# nandboard.net
KiCad netlist of a schematic drawn in EAGLE
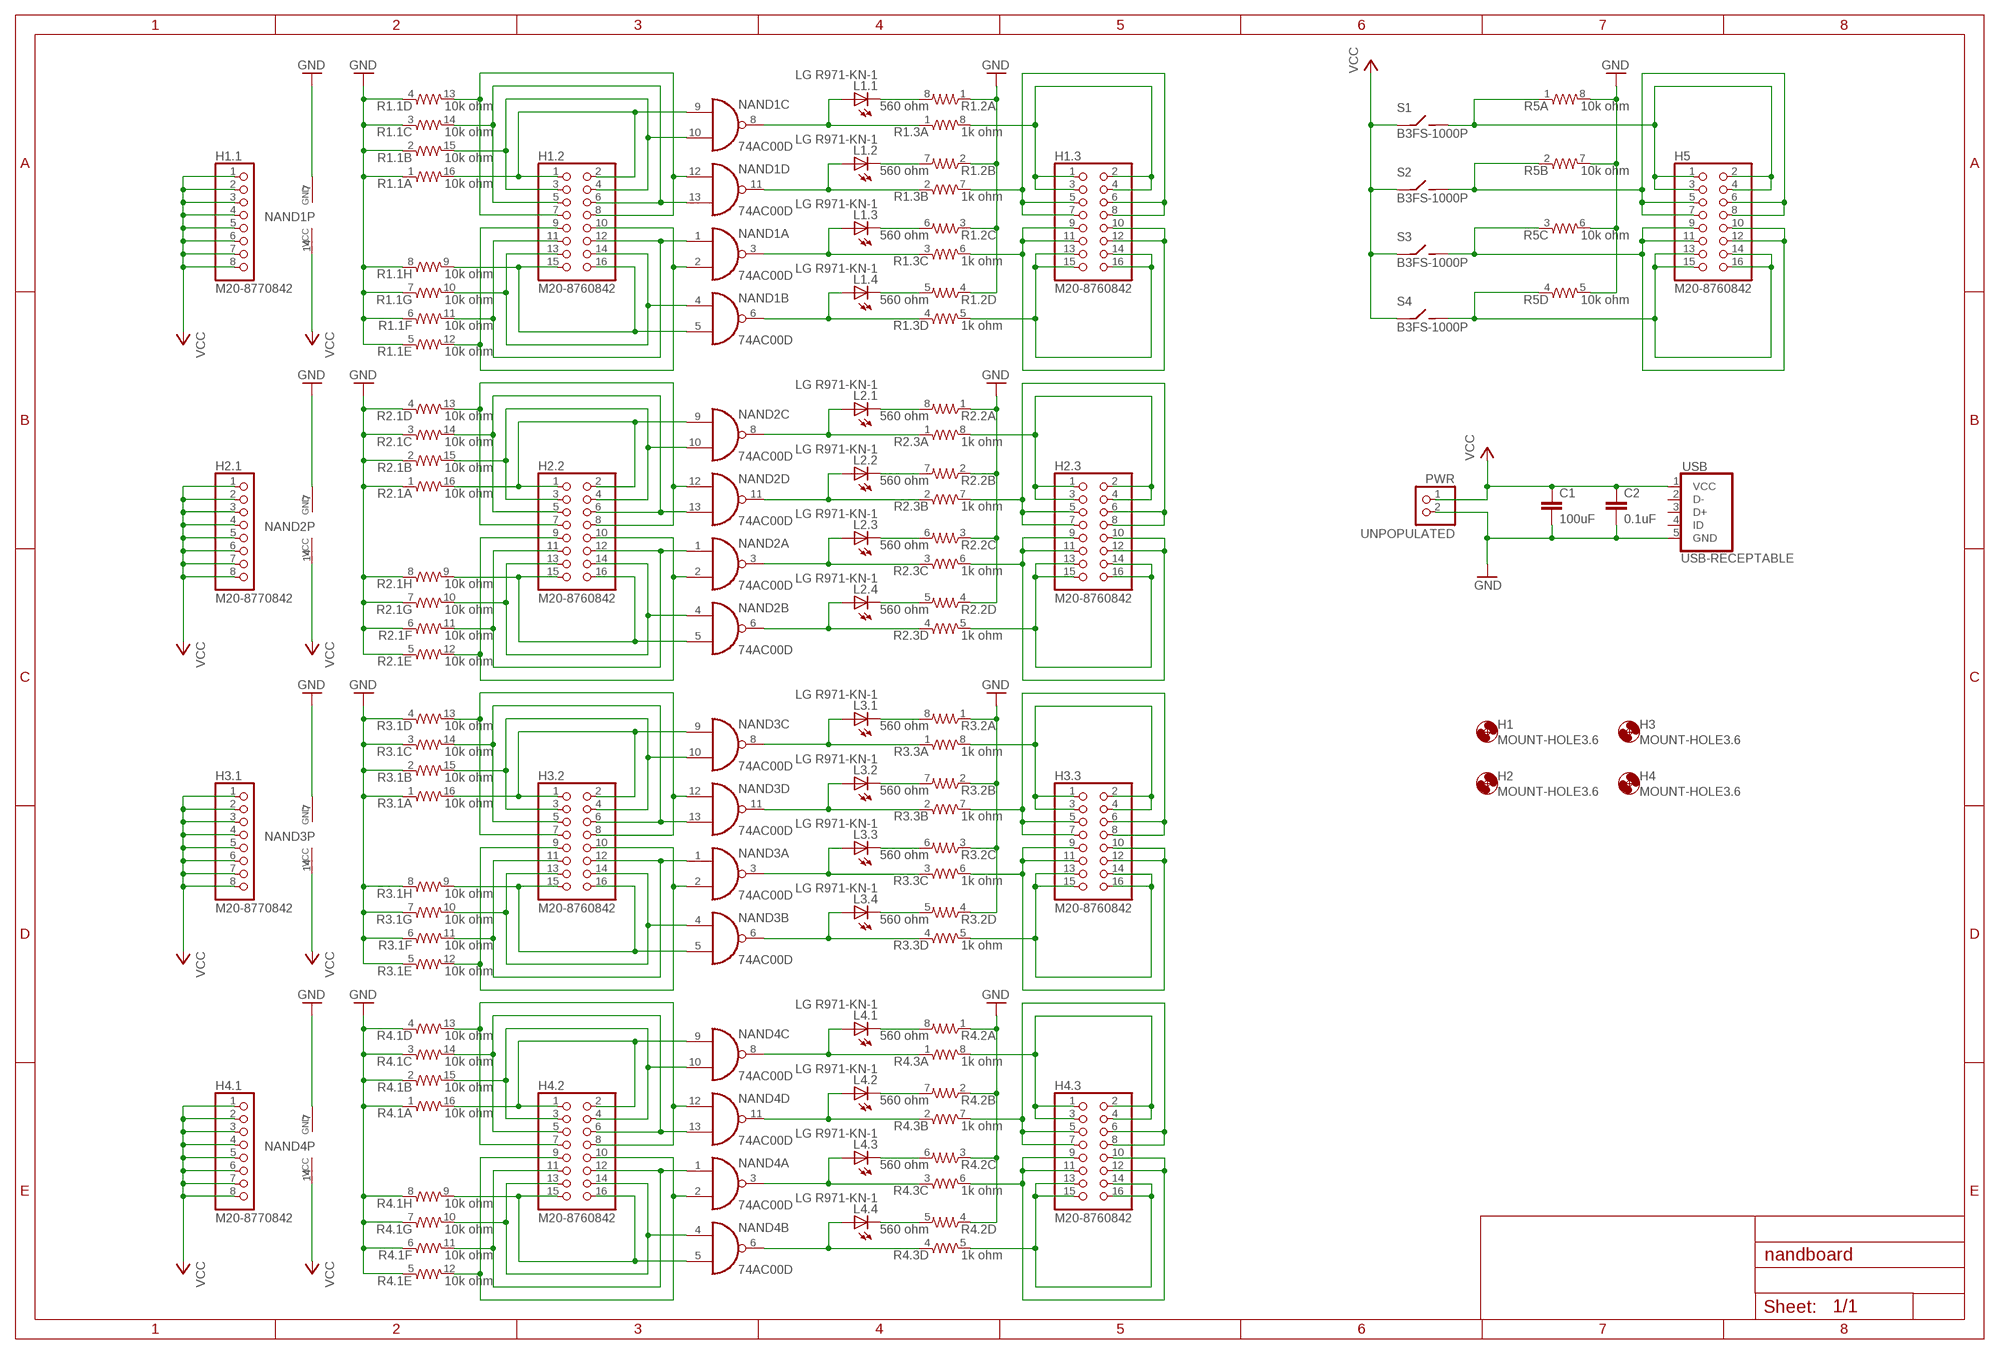
[diagram p0: schematic, sheet 1]

(export (version "E")
  (design (tool "Eeschema 10.0.6"))
  (components
    (comp (ref "C1")
      (value "100uF")
      (footprint "eagle-import:C1210")
      (libsource (lib "eagle-import") (part "C-EUC1210"))
    )
    (comp (ref "C2")
      (value "0.1uF")
      (footprint "eagle-import:C0805")
      (libsource (lib "eagle-import") (part "C-EUC0805"))
    )
    (comp (ref "H1")
      (value "MOUNT-HOLE3.6")
      (footprint "eagle-import:3,6")
      (libsource (lib "eagle-import") (part "MOUNT-HOLE3.6"))
    )
    (comp (ref "H1.1")
      (value "M20-8770842")
      (footprint "eagle-import:1X08_SMT")
      (libsource (lib "eagle-import") (part "PINHD-1X81X08_SMT"))
    )
    (comp (ref "H1.2")
      (value "M20-8760842")
      (footprint "eagle-import:2X08_SMT")
      (libsource (lib "eagle-import") (part "PINHD-2X8SMT"))
    )
    (comp (ref "H1.3")
      (value "M20-8760842")
      (footprint "eagle-import:2X08_SMT")
      (libsource (lib "eagle-import") (part "PINHD-2X8SMT"))
    )
    (comp (ref "H2")
      (value "MOUNT-HOLE3.6")
      (footprint "eagle-import:3,6")
      (libsource (lib "eagle-import") (part "MOUNT-HOLE3.6"))
    )
    (comp (ref "H2.1")
      (value "M20-8770842")
      (footprint "eagle-import:1X08_SMT")
      (libsource (lib "eagle-import") (part "PINHD-1X81X08_SMT"))
    )
    (comp (ref "H2.2")
      (value "M20-8760842")
      (footprint "eagle-import:2X08_SMT")
      (libsource (lib "eagle-import") (part "PINHD-2X8SMT"))
    )
    (comp (ref "H2.3")
      (value "M20-8760842")
      (footprint "eagle-import:2X08_SMT")
      (libsource (lib "eagle-import") (part "PINHD-2X8SMT"))
    )
    (comp (ref "H3")
      (value "MOUNT-HOLE3.6")
      (footprint "eagle-import:3,6")
      (libsource (lib "eagle-import") (part "MOUNT-HOLE3.6"))
    )
    (comp (ref "H3.1")
      (value "M20-8770842")
      (footprint "eagle-import:1X08_SMT")
      (libsource (lib "eagle-import") (part "PINHD-1X81X08_SMT"))
    )
    (comp (ref "H3.2")
      (value "M20-8760842")
      (footprint "eagle-import:2X08_SMT")
      (libsource (lib "eagle-import") (part "PINHD-2X8SMT"))
    )
    (comp (ref "H3.3")
      (value "M20-8760842")
      (footprint "eagle-import:2X08_SMT")
      (libsource (lib "eagle-import") (part "PINHD-2X8SMT"))
    )
    (comp (ref "H4")
      (value "MOUNT-HOLE3.6")
      (footprint "eagle-import:3,6")
      (libsource (lib "eagle-import") (part "MOUNT-HOLE3.6"))
    )
    (comp (ref "H4.1")
      (value "M20-8770842")
      (footprint "eagle-import:1X08_SMT")
      (libsource (lib "eagle-import") (part "PINHD-1X81X08_SMT"))
    )
    (comp (ref "H4.2")
      (value "M20-8760842")
      (footprint "eagle-import:2X08_SMT")
      (libsource (lib "eagle-import") (part "PINHD-2X8SMT"))
    )
    (comp (ref "H4.3")
      (value "M20-8760842")
      (footprint "eagle-import:2X08_SMT")
      (libsource (lib "eagle-import") (part "PINHD-2X8SMT"))
    )
    (comp (ref "H5")
      (value "M20-8760842")
      (footprint "eagle-import:2X08_SMT")
      (libsource (lib "eagle-import") (part "PINHD-2X8SMT"))
    )
    (comp (ref "L1.1")
      (value "LG R971-KN-1")
      (footprint "eagle-import:CHIPLED_0805")
      (libsource (lib "eagle-import") (part "LEDCHIPLED_0805"))
    )
    (comp (ref "L1.2")
      (value "LG R971-KN-1")
      (footprint "eagle-import:CHIPLED_0805")
      (libsource (lib "eagle-import") (part "LEDCHIPLED_0805"))
    )
    (comp (ref "L1.3")
      (value "LG R971-KN-1")
      (footprint "eagle-import:CHIPLED_0805")
      (libsource (lib "eagle-import") (part "LEDCHIPLED_0805"))
    )
    (comp (ref "L1.4")
      (value "LG R971-KN-1")
      (footprint "eagle-import:CHIPLED_0805")
      (libsource (lib "eagle-import") (part "LEDCHIPLED_0805"))
    )
    (comp (ref "L2.1")
      (value "LG R971-KN-1")
      (footprint "eagle-import:CHIPLED_0805")
      (libsource (lib "eagle-import") (part "LEDCHIPLED_0805"))
    )
    (comp (ref "L2.2")
      (value "LG R971-KN-1")
      (footprint "eagle-import:CHIPLED_0805")
      (libsource (lib "eagle-import") (part "LEDCHIPLED_0805"))
    )
    (comp (ref "L2.3")
      (value "LG R971-KN-1")
      (footprint "eagle-import:CHIPLED_0805")
      (libsource (lib "eagle-import") (part "LEDCHIPLED_0805"))
    )
    (comp (ref "L2.4")
      (value "LG R971-KN-1")
      (footprint "eagle-import:CHIPLED_0805")
      (libsource (lib "eagle-import") (part "LEDCHIPLED_0805"))
    )
    (comp (ref "L3.1")
      (value "LG R971-KN-1")
      (footprint "eagle-import:CHIPLED_0805")
      (libsource (lib "eagle-import") (part "LEDCHIPLED_0805"))
    )
    (comp (ref "L3.2")
      (value "LG R971-KN-1")
      (footprint "eagle-import:CHIPLED_0805")
      (libsource (lib "eagle-import") (part "LEDCHIPLED_0805"))
    )
    (comp (ref "L3.3")
      (value "LG R971-KN-1")
      (footprint "eagle-import:CHIPLED_0805")
      (libsource (lib "eagle-import") (part "LEDCHIPLED_0805"))
    )
    (comp (ref "L3.4")
      (value "LG R971-KN-1")
      (footprint "eagle-import:CHIPLED_0805")
      (libsource (lib "eagle-import") (part "LEDCHIPLED_0805"))
    )
    (comp (ref "L4.1")
      (value "LG R971-KN-1")
      (footprint "eagle-import:CHIPLED_0805")
      (libsource (lib "eagle-import") (part "LEDCHIPLED_0805"))
    )
    (comp (ref "L4.2")
      (value "LG R971-KN-1")
      (footprint "eagle-import:CHIPLED_0805")
      (libsource (lib "eagle-import") (part "LEDCHIPLED_0805"))
    )
    (comp (ref "L4.3")
      (value "LG R971-KN-1")
      (footprint "eagle-import:CHIPLED_0805")
      (libsource (lib "eagle-import") (part "LEDCHIPLED_0805"))
    )
    (comp (ref "L4.4")
      (value "LG R971-KN-1")
      (footprint "eagle-import:CHIPLED_0805")
      (libsource (lib "eagle-import") (part "LEDCHIPLED_0805"))
    )
    (comp (ref "NAND1")
      (value "74AC00D")
      (footprint "eagle-import:SO14")
      (libsource (lib "eagle-import") (part "7400DAC"))
    )
    (comp (ref "NAND2")
      (value "74AC00D")
      (footprint "eagle-import:SO14")
      (libsource (lib "eagle-import") (part "7400DAC"))
    )
    (comp (ref "NAND3")
      (value "74AC00D")
      (footprint "eagle-import:SO14")
      (libsource (lib "eagle-import") (part "7400DAC"))
    )
    (comp (ref "NAND4")
      (value "74AC00D")
      (footprint "eagle-import:SO14")
      (libsource (lib "eagle-import") (part "7400DAC"))
    )
    (comp (ref "PWR")
      (value "UNPOPULATED")
      (footprint "eagle-import:1X02")
      (libsource (lib "eagle-import") (part "PINHD-1X2"))
    )
    (comp (ref "R1.1")
      (value "10k ohm")
      (footprint "eagle-import:742-16")
      (libsource (lib "eagle-import") (part "742-16_S"))
    )
    (comp (ref "R1.2")
      (value "560 ohm")
      (footprint "eagle-import:742-8")
      (libsource (lib "eagle-import") (part "742-8_S"))
    )
    (comp (ref "R1.3")
      (value "1k ohm")
      (footprint "eagle-import:742-8")
      (libsource (lib "eagle-import") (part "742-8_S"))
    )
    (comp (ref "R2.1")
      (value "10k ohm")
      (footprint "eagle-import:742-16")
      (libsource (lib "eagle-import") (part "742-16_S"))
    )
    (comp (ref "R2.2")
      (value "560 ohm")
      (footprint "eagle-import:742-8")
      (libsource (lib "eagle-import") (part "742-8_S"))
    )
    (comp (ref "R2.3")
      (value "1k ohm")
      (footprint "eagle-import:742-8")
      (libsource (lib "eagle-import") (part "742-8_S"))
    )
    (comp (ref "R3.1")
      (value "10k ohm")
      (footprint "eagle-import:742-16")
      (libsource (lib "eagle-import") (part "742-16_S"))
    )
    (comp (ref "R3.2")
      (value "560 ohm")
      (footprint "eagle-import:742-8")
      (libsource (lib "eagle-import") (part "742-8_S"))
    )
    (comp (ref "R3.3")
      (value "1k ohm")
      (footprint "eagle-import:742-8")
      (libsource (lib "eagle-import") (part "742-8_S"))
    )
    (comp (ref "R4.1")
      (value "10k ohm")
      (footprint "eagle-import:742-16")
      (libsource (lib "eagle-import") (part "742-16_S"))
    )
    (comp (ref "R4.2")
      (value "560 ohm")
      (footprint "eagle-import:742-8")
      (libsource (lib "eagle-import") (part "742-8_S"))
    )
    (comp (ref "R4.3")
      (value "1k ohm")
      (footprint "eagle-import:742-8")
      (libsource (lib "eagle-import") (part "742-8_S"))
    )
    (comp (ref "R5")
      (value "10k ohm")
      (footprint "eagle-import:742-8")
      (libsource (lib "eagle-import") (part "742-8_S"))
    )
    (comp (ref "S1")
      (value "B3FS-1000P")
      (footprint "eagle-import:B3FS-1000")
      (libsource (lib "eagle-import") (part "SPSTB3FS-1000"))
    )
    (comp (ref "S2")
      (value "B3FS-1000P")
      (footprint "eagle-import:B3FS-1000")
      (libsource (lib "eagle-import") (part "SPSTB3FS-1000"))
    )
    (comp (ref "S3")
      (value "B3FS-1000P")
      (footprint "eagle-import:B3FS-1000")
      (libsource (lib "eagle-import") (part "SPSTB3FS-1000"))
    )
    (comp (ref "S4")
      (value "B3FS-1000P")
      (footprint "eagle-import:B3FS-1000")
      (libsource (lib "eagle-import") (part "SPSTB3FS-1000"))
    )
    (comp (ref "USB")
      (value "USB-RECEPTABLE")
      (footprint "eagle-import:FCI-10103594-0001LF")
      (libsource (lib "eagle-import") (part "USB-RECEPTABLE"))
    )
  )
  (nets
    (net (code "1") (name "GND") (class "Default")
      (node (ref "C1") (pin "2") (pinfunction "2_2") (pintype "passive"))
      (node (ref "C2") (pin "2") (pinfunction "2_2") (pintype "passive"))
      (node (ref "NAND1") (pin "7") (pinfunction "GND_7") (pintype "power_in"))
      (node (ref "NAND2") (pin "7") (pinfunction "GND_7") (pintype "power_in"))
      (node (ref "NAND3") (pin "7") (pinfunction "GND_7") (pintype "power_in"))
      (node (ref "NAND4") (pin "7") (pinfunction "GND_7") (pintype "power_in"))
      (node (ref "PWR") (pin "2") (pinfunction "2_2") (pintype "passive"))
      (node (ref "R1.1") (pin "1") (pinfunction "1_1") (pintype "passive"))
      (node (ref "R1.1") (pin "2") (pinfunction "1_2") (pintype "passive"))
      (node (ref "R1.1") (pin "3") (pinfunction "1_3") (pintype "passive"))
      (node (ref "R1.1") (pin "4") (pinfunction "1_4") (pintype "passive"))
      (node (ref "R1.1") (pin "5") (pinfunction "1_5") (pintype "passive"))
      (node (ref "R1.1") (pin "6") (pinfunction "1_6") (pintype "passive"))
      (node (ref "R1.1") (pin "7") (pinfunction "1_7") (pintype "passive"))
      (node (ref "R1.1") (pin "8") (pinfunction "1_8") (pintype "passive"))
      (node (ref "R1.2") (pin "1") (pinfunction "1_1") (pintype "passive"))
      (node (ref "R1.2") (pin "2") (pinfunction "1_2") (pintype "passive"))
      (node (ref "R1.2") (pin "3") (pinfunction "1_3") (pintype "passive"))
      (node (ref "R1.2") (pin "4") (pinfunction "1_4") (pintype "passive"))
      (node (ref "R2.1") (pin "1") (pinfunction "1_1") (pintype "passive"))
      (node (ref "R2.1") (pin "2") (pinfunction "1_2") (pintype "passive"))
      (node (ref "R2.1") (pin "3") (pinfunction "1_3") (pintype "passive"))
      (node (ref "R2.1") (pin "4") (pinfunction "1_4") (pintype "passive"))
      (node (ref "R2.1") (pin "5") (pinfunction "1_5") (pintype "passive"))
      (node (ref "R2.1") (pin "6") (pinfunction "1_6") (pintype "passive"))
      (node (ref "R2.1") (pin "7") (pinfunction "1_7") (pintype "passive"))
      (node (ref "R2.1") (pin "8") (pinfunction "1_8") (pintype "passive"))
      (node (ref "R2.2") (pin "1") (pinfunction "1_1") (pintype "passive"))
      (node (ref "R2.2") (pin "2") (pinfunction "1_2") (pintype "passive"))
      (node (ref "R2.2") (pin "3") (pinfunction "1_3") (pintype "passive"))
      (node (ref "R2.2") (pin "4") (pinfunction "1_4") (pintype "passive"))
      (node (ref "R3.1") (pin "1") (pinfunction "1_1") (pintype "passive"))
      (node (ref "R3.1") (pin "2") (pinfunction "1_2") (pintype "passive"))
      (node (ref "R3.1") (pin "3") (pinfunction "1_3") (pintype "passive"))
      (node (ref "R3.1") (pin "4") (pinfunction "1_4") (pintype "passive"))
      (node (ref "R3.1") (pin "5") (pinfunction "1_5") (pintype "passive"))
      (node (ref "R3.1") (pin "6") (pinfunction "1_6") (pintype "passive"))
      (node (ref "R3.1") (pin "7") (pinfunction "1_7") (pintype "passive"))
      (node (ref "R3.1") (pin "8") (pinfunction "1_8") (pintype "passive"))
      (node (ref "R3.2") (pin "1") (pinfunction "1_1") (pintype "passive"))
      (node (ref "R3.2") (pin "2") (pinfunction "1_2") (pintype "passive"))
      (node (ref "R3.2") (pin "3") (pinfunction "1_3") (pintype "passive"))
      (node (ref "R3.2") (pin "4") (pinfunction "1_4") (pintype "passive"))
      (node (ref "R4.1") (pin "1") (pinfunction "1_1") (pintype "passive"))
      (node (ref "R4.1") (pin "2") (pinfunction "1_2") (pintype "passive"))
      (node (ref "R4.1") (pin "3") (pinfunction "1_3") (pintype "passive"))
      (node (ref "R4.1") (pin "4") (pinfunction "1_4") (pintype "passive"))
      (node (ref "R4.1") (pin "5") (pinfunction "1_5") (pintype "passive"))
      (node (ref "R4.1") (pin "6") (pinfunction "1_6") (pintype "passive"))
      (node (ref "R4.1") (pin "7") (pinfunction "1_7") (pintype "passive"))
      (node (ref "R4.1") (pin "8") (pinfunction "1_8") (pintype "passive"))
      (node (ref "R4.2") (pin "1") (pinfunction "1_1") (pintype "passive"))
      (node (ref "R4.2") (pin "2") (pinfunction "1_2") (pintype "passive"))
      (node (ref "R4.2") (pin "3") (pinfunction "1_3") (pintype "passive"))
      (node (ref "R4.2") (pin "4") (pinfunction "1_4") (pintype "passive"))
      (node (ref "R5") (pin "5") (pinfunction "2_5") (pintype "passive"))
      (node (ref "R5") (pin "6") (pinfunction "2_6") (pintype "passive"))
      (node (ref "R5") (pin "7") (pinfunction "2_7") (pintype "passive"))
      (node (ref "R5") (pin "8") (pinfunction "2_8") (pintype "passive"))
      (node (ref "USB") (pin "5") (pinfunction "GND_5") (pintype "bidirectional"))
    )
    (net (code "2") (name "Net-(H5-Pad1)") (class "Default")
      (node (ref "H5") (pin "1") (pinfunction "1_1") (pintype "passive"))
      (node (ref "H5") (pin "2") (pinfunction "2_2") (pintype "passive"))
      (node (ref "H5") (pin "3") (pinfunction "3_3") (pintype "passive"))
      (node (ref "H5") (pin "4") (pinfunction "4_4") (pintype "passive"))
      (node (ref "R5") (pin "1") (pinfunction "1_1") (pintype "passive"))
      (node (ref "S1") (pin "3") (pinfunction "B_3") (pintype "bidirectional"))
      (node (ref "S1") (pin "4") (pinfunction "B_4") (pintype "bidirectional"))
    )
    (net (code "3") (name "Net-(NAND1A-I0)") (class "Default")
      (node (ref "H1.2") (pin "11") (pinfunction "11_11") (pintype "passive"))
      (node (ref "H1.2") (pin "12") (pinfunction "12_12") (pintype "passive"))
      (node (ref "NAND1") (pin "1") (pinfunction "I0_1") (pintype "input"))
      (node (ref "R1.1") (pin "11") (pinfunction "2_11") (pintype "passive"))
    )
    (net (code "4") (name "Net-(NAND1A-I1)") (class "Default")
      (node (ref "H1.2") (pin "10") (pinfunction "10_10") (pintype "passive"))
      (node (ref "H1.2") (pin "9") (pinfunction "9_9") (pintype "passive"))
      (node (ref "NAND1") (pin "2") (pinfunction "I1_2") (pintype "input"))
      (node (ref "R1.1") (pin "12") (pinfunction "2_12") (pintype "passive"))
    )
    (net (code "5") (name "Net-(NAND1A-O)") (class "Default")
      (node (ref "L1.3") (pin "A") (pinfunction "A_A") (pintype "passive"))
      (node (ref "NAND1") (pin "3") (pinfunction "O_3") (pintype "output"))
      (node (ref "R1.3") (pin "3") (pinfunction "1_3") (pintype "passive"))
    )
    (net (code "6") (name "Net-(NAND1B-I0)") (class "Default")
      (node (ref "H1.2") (pin "13") (pinfunction "13_13") (pintype "passive"))
      (node (ref "H1.2") (pin "14") (pinfunction "14_14") (pintype "passive"))
      (node (ref "NAND1") (pin "4") (pinfunction "I0_4") (pintype "input"))
      (node (ref "R1.1") (pin "10") (pinfunction "2_10") (pintype "passive"))
    )
    (net (code "7") (name "Net-(NAND1B-I1)") (class "Default")
      (node (ref "H1.2") (pin "15") (pinfunction "15_15") (pintype "passive"))
      (node (ref "H1.2") (pin "16") (pinfunction "16_16") (pintype "passive"))
      (node (ref "NAND1") (pin "5") (pinfunction "I1_5") (pintype "input"))
      (node (ref "R1.1") (pin "9") (pinfunction "2_9") (pintype "passive"))
    )
    (net (code "8") (name "Net-(NAND1B-O)") (class "Default")
      (node (ref "L1.4") (pin "A") (pinfunction "A_A") (pintype "passive"))
      (node (ref "NAND1") (pin "6") (pinfunction "O_6") (pintype "output"))
      (node (ref "R1.3") (pin "4") (pinfunction "1_4") (pintype "passive"))
    )
    (net (code "9") (name "Net-(NAND1C-I0)") (class "Default")
      (node (ref "H1.2") (pin "1") (pinfunction "1_1") (pintype "passive"))
      (node (ref "H1.2") (pin "2") (pinfunction "2_2") (pintype "passive"))
      (node (ref "NAND1") (pin "9") (pinfunction "I0_9") (pintype "input"))
      (node (ref "R1.1") (pin "16") (pinfunction "2_16") (pintype "passive"))
    )
    (net (code "10") (name "Net-(NAND1C-I1)") (class "Default")
      (node (ref "H1.2") (pin "3") (pinfunction "3_3") (pintype "passive"))
      (node (ref "H1.2") (pin "4") (pinfunction "4_4") (pintype "passive"))
      (node (ref "NAND1") (pin "10") (pinfunction "I1_10") (pintype "input"))
      (node (ref "R1.1") (pin "15") (pinfunction "2_15") (pintype "passive"))
    )
    (net (code "11") (name "Net-(NAND1C-O)") (class "Default")
      (node (ref "L1.1") (pin "A") (pinfunction "A_A") (pintype "passive"))
      (node (ref "NAND1") (pin "8") (pinfunction "O_8") (pintype "output"))
      (node (ref "R1.3") (pin "1") (pinfunction "1_1") (pintype "passive"))
    )
    (net (code "12") (name "Net-(NAND1D-I0)") (class "Default")
      (node (ref "H1.2") (pin "7") (pinfunction "7_7") (pintype "passive"))
      (node (ref "H1.2") (pin "8") (pinfunction "8_8") (pintype "passive"))
      (node (ref "NAND1") (pin "12") (pinfunction "I0_12") (pintype "input"))
      (node (ref "R1.1") (pin "13") (pinfunction "2_13") (pintype "passive"))
    )
    (net (code "13") (name "Net-(NAND1D-I1)") (class "Default")
      (node (ref "H1.2") (pin "5") (pinfunction "5_5") (pintype "passive"))
      (node (ref "H1.2") (pin "6") (pinfunction "6_6") (pintype "passive"))
      (node (ref "NAND1") (pin "13") (pinfunction "I1_13") (pintype "input"))
      (node (ref "R1.1") (pin "14") (pinfunction "2_14") (pintype "passive"))
    )
    (net (code "14") (name "Net-(NAND1D-O)") (class "Default")
      (node (ref "L1.2") (pin "A") (pinfunction "A_A") (pintype "passive"))
      (node (ref "NAND1") (pin "11") (pinfunction "O_11") (pintype "output"))
      (node (ref "R1.3") (pin "2") (pinfunction "1_2") (pintype "passive"))
    )
    (net (code "15") (name "Net-(NAND2A-I0)") (class "Default")
      (node (ref "H2.2") (pin "11") (pinfunction "11_11") (pintype "passive"))
      (node (ref "H2.2") (pin "12") (pinfunction "12_12") (pintype "passive"))
      (node (ref "NAND2") (pin "1") (pinfunction "I0_1") (pintype "input"))
      (node (ref "R2.1") (pin "11") (pinfunction "2_11") (pintype "passive"))
    )
    (net (code "16") (name "Net-(NAND2A-I1)") (class "Default")
      (node (ref "H2.2") (pin "10") (pinfunction "10_10") (pintype "passive"))
      (node (ref "H2.2") (pin "9") (pinfunction "9_9") (pintype "passive"))
      (node (ref "NAND2") (pin "2") (pinfunction "I1_2") (pintype "input"))
      (node (ref "R2.1") (pin "12") (pinfunction "2_12") (pintype "passive"))
    )
    (net (code "17") (name "Net-(NAND2A-O)") (class "Default")
      (node (ref "L2.3") (pin "A") (pinfunction "A_A") (pintype "passive"))
      (node (ref "NAND2") (pin "3") (pinfunction "O_3") (pintype "output"))
      (node (ref "R2.3") (pin "3") (pinfunction "1_3") (pintype "passive"))
    )
    (net (code "18") (name "Net-(NAND2B-I0)") (class "Default")
      (node (ref "H2.2") (pin "13") (pinfunction "13_13") (pintype "passive"))
      (node (ref "H2.2") (pin "14") (pinfunction "14_14") (pintype "passive"))
      (node (ref "NAND2") (pin "4") (pinfunction "I0_4") (pintype "input"))
      (node (ref "R2.1") (pin "10") (pinfunction "2_10") (pintype "passive"))
    )
    (net (code "19") (name "Net-(NAND2B-I1)") (class "Default")
      (node (ref "H2.2") (pin "15") (pinfunction "15_15") (pintype "passive"))
      (node (ref "H2.2") (pin "16") (pinfunction "16_16") (pintype "passive"))
      (node (ref "NAND2") (pin "5") (pinfunction "I1_5") (pintype "input"))
      (node (ref "R2.1") (pin "9") (pinfunction "2_9") (pintype "passive"))
    )
    (net (code "20") (name "Net-(NAND2B-O)") (class "Default")
      (node (ref "L2.4") (pin "A") (pinfunction "A_A") (pintype "passive"))
      (node (ref "NAND2") (pin "6") (pinfunction "O_6") (pintype "output"))
      (node (ref "R2.3") (pin "4") (pinfunction "1_4") (pintype "passive"))
    )
    (net (code "21") (name "Net-(NAND2C-I0)") (class "Default")
      (node (ref "H2.2") (pin "1") (pinfunction "1_1") (pintype "passive"))
      (node (ref "H2.2") (pin "2") (pinfunction "2_2") (pintype "passive"))
      (node (ref "NAND2") (pin "9") (pinfunction "I0_9") (pintype "input"))
      (node (ref "R2.1") (pin "16") (pinfunction "2_16") (pintype "passive"))
    )
    (net (code "22") (name "Net-(NAND2C-I1)") (class "Default")
      (node (ref "H2.2") (pin "3") (pinfunction "3_3") (pintype "passive"))
      (node (ref "H2.2") (pin "4") (pinfunction "4_4") (pintype "passive"))
      (node (ref "NAND2") (pin "10") (pinfunction "I1_10") (pintype "input"))
      (node (ref "R2.1") (pin "15") (pinfunction "2_15") (pintype "passive"))
    )
    (net (code "23") (name "Net-(NAND2C-O)") (class "Default")
      (node (ref "L2.1") (pin "A") (pinfunction "A_A") (pintype "passive"))
      (node (ref "NAND2") (pin "8") (pinfunction "O_8") (pintype "output"))
      (node (ref "R2.3") (pin "1") (pinfunction "1_1") (pintype "passive"))
    )
    (net (code "24") (name "Net-(NAND2D-I0)") (class "Default")
      (node (ref "H2.2") (pin "7") (pinfunction "7_7") (pintype "passive"))
      (node (ref "H2.2") (pin "8") (pinfunction "8_8") (pintype "passive"))
      (node (ref "NAND2") (pin "12") (pinfunction "I0_12") (pintype "input"))
      (node (ref "R2.1") (pin "13") (pinfunction "2_13") (pintype "passive"))
    )
    (net (code "25") (name "Net-(NAND2D-I1)") (class "Default")
      (node (ref "H2.2") (pin "5") (pinfunction "5_5") (pintype "passive"))
      (node (ref "H2.2") (pin "6") (pinfunction "6_6") (pintype "passive"))
      (node (ref "NAND2") (pin "13") (pinfunction "I1_13") (pintype "input"))
      (node (ref "R2.1") (pin "14") (pinfunction "2_14") (pintype "passive"))
    )
    (net (code "26") (name "Net-(NAND2D-O)") (class "Default")
      (node (ref "L2.2") (pin "A") (pinfunction "A_A") (pintype "passive"))
      (node (ref "NAND2") (pin "11") (pinfunction "O_11") (pintype "output"))
      (node (ref "R2.3") (pin "2") (pinfunction "1_2") (pintype "passive"))
    )
    (net (code "27") (name "Net-(NAND3A-I0)") (class "Default")
      (node (ref "H3.2") (pin "11") (pinfunction "11_11") (pintype "passive"))
      (node (ref "H3.2") (pin "12") (pinfunction "12_12") (pintype "passive"))
      (node (ref "NAND3") (pin "1") (pinfunction "I0_1") (pintype "input"))
      (node (ref "R3.1") (pin "11") (pinfunction "2_11") (pintype "passive"))
    )
    (net (code "28") (name "Net-(NAND3A-I1)") (class "Default")
      (node (ref "H3.2") (pin "10") (pinfunction "10_10") (pintype "passive"))
      (node (ref "H3.2") (pin "9") (pinfunction "9_9") (pintype "passive"))
      (node (ref "NAND3") (pin "2") (pinfunction "I1_2") (pintype "input"))
      (node (ref "R3.1") (pin "12") (pinfunction "2_12") (pintype "passive"))
    )
    (net (code "29") (name "Net-(NAND3A-O)") (class "Default")
      (node (ref "L3.3") (pin "A") (pinfunction "A_A") (pintype "passive"))
      (node (ref "NAND3") (pin "3") (pinfunction "O_3") (pintype "output"))
      (node (ref "R3.3") (pin "3") (pinfunction "1_3") (pintype "passive"))
    )
    (net (code "30") (name "Net-(NAND3B-I0)") (class "Default")
      (node (ref "H3.2") (pin "13") (pinfunction "13_13") (pintype "passive"))
      (node (ref "H3.2") (pin "14") (pinfunction "14_14") (pintype "passive"))
      (node (ref "NAND3") (pin "4") (pinfunction "I0_4") (pintype "input"))
      (node (ref "R3.1") (pin "10") (pinfunction "2_10") (pintype "passive"))
    )
    (net (code "31") (name "Net-(NAND3B-I1)") (class "Default")
      (node (ref "H3.2") (pin "15") (pinfunction "15_15") (pintype "passive"))
      (node (ref "H3.2") (pin "16") (pinfunction "16_16") (pintype "passive"))
      (node (ref "NAND3") (pin "5") (pinfunction "I1_5") (pintype "input"))
      (node (ref "R3.1") (pin "9") (pinfunction "2_9") (pintype "passive"))
    )
    (net (code "32") (name "Net-(NAND3B-O)") (class "Default")
      (node (ref "L3.4") (pin "A") (pinfunction "A_A") (pintype "passive"))
      (node (ref "NAND3") (pin "6") (pinfunction "O_6") (pintype "output"))
      (node (ref "R3.3") (pin "4") (pinfunction "1_4") (pintype "passive"))
    )
    (net (code "33") (name "Net-(NAND3C-I0)") (class "Default")
      (node (ref "H3.2") (pin "1") (pinfunction "1_1") (pintype "passive"))
      (node (ref "H3.2") (pin "2") (pinfunction "2_2") (pintype "passive"))
      (node (ref "NAND3") (pin "9") (pinfunction "I0_9") (pintype "input"))
      (node (ref "R3.1") (pin "16") (pinfunction "2_16") (pintype "passive"))
    )
    (net (code "34") (name "Net-(NAND3C-I1)") (class "Default")
      (node (ref "H3.2") (pin "3") (pinfunction "3_3") (pintype "passive"))
      (node (ref "H3.2") (pin "4") (pinfunction "4_4") (pintype "passive"))
      (node (ref "NAND3") (pin "10") (pinfunction "I1_10") (pintype "input"))
      (node (ref "R3.1") (pin "15") (pinfunction "2_15") (pintype "passive"))
    )
    (net (code "35") (name "Net-(NAND3C-O)") (class "Default")
      (node (ref "L3.1") (pin "A") (pinfunction "A_A") (pintype "passive"))
      (node (ref "NAND3") (pin "8") (pinfunction "O_8") (pintype "output"))
      (node (ref "R3.3") (pin "1") (pinfunction "1_1") (pintype "passive"))
    )
    (net (code "36") (name "Net-(NAND3D-I0)") (class "Default")
      (node (ref "H3.2") (pin "7") (pinfunction "7_7") (pintype "passive"))
      (node (ref "H3.2") (pin "8") (pinfunction "8_8") (pintype "passive"))
      (node (ref "NAND3") (pin "12") (pinfunction "I0_12") (pintype "input"))
      (node (ref "R3.1") (pin "13") (pinfunction "2_13") (pintype "passive"))
    )
    (net (code "37") (name "Net-(NAND3D-I1)") (class "Default")
      (node (ref "H3.2") (pin "5") (pinfunction "5_5") (pintype "passive"))
      (node (ref "H3.2") (pin "6") (pinfunction "6_6") (pintype "passive"))
      (node (ref "NAND3") (pin "13") (pinfunction "I1_13") (pintype "input"))
      (node (ref "R3.1") (pin "14") (pinfunction "2_14") (pintype "passive"))
    )
    (net (code "38") (name "Net-(NAND3D-O)") (class "Default")
      (node (ref "L3.2") (pin "A") (pinfunction "A_A") (pintype "passive"))
      (node (ref "NAND3") (pin "11") (pinfunction "O_11") (pintype "output"))
      (node (ref "R3.3") (pin "2") (pinfunction "1_2") (pintype "passive"))
    )
    (net (code "39") (name "Net-(NAND4A-I0)") (class "Default")
      (node (ref "H4.2") (pin "11") (pinfunction "11_11") (pintype "passive"))
      (node (ref "H4.2") (pin "12") (pinfunction "12_12") (pintype "passive"))
      (node (ref "NAND4") (pin "1") (pinfunction "I0_1") (pintype "input"))
      (node (ref "R4.1") (pin "11") (pinfunction "2_11") (pintype "passive"))
    )
    (net (code "40") (name "Net-(NAND4A-I1)") (class "Default")
      (node (ref "H4.2") (pin "10") (pinfunction "10_10") (pintype "passive"))
      (node (ref "H4.2") (pin "9") (pinfunction "9_9") (pintype "passive"))
      (node (ref "NAND4") (pin "2") (pinfunction "I1_2") (pintype "input"))
      (node (ref "R4.1") (pin "12") (pinfunction "2_12") (pintype "passive"))
    )
    (net (code "41") (name "Net-(NAND4A-O)") (class "Default")
      (node (ref "L4.3") (pin "A") (pinfunction "A_A") (pintype "passive"))
      (node (ref "NAND4") (pin "3") (pinfunction "O_3") (pintype "output"))
      (node (ref "R4.3") (pin "3") (pinfunction "1_3") (pintype "passive"))
    )
    (net (code "42") (name "Net-(NAND4B-I0)") (class "Default")
      (node (ref "H4.2") (pin "13") (pinfunction "13_13") (pintype "passive"))
      (node (ref "H4.2") (pin "14") (pinfunction "14_14") (pintype "passive"))
      (node (ref "NAND4") (pin "4") (pinfunction "I0_4") (pintype "input"))
      (node (ref "R4.1") (pin "10") (pinfunction "2_10") (pintype "passive"))
    )
    (net (code "43") (name "Net-(NAND4B-I1)") (class "Default")
      (node (ref "H4.2") (pin "15") (pinfunction "15_15") (pintype "passive"))
      (node (ref "H4.2") (pin "16") (pinfunction "16_16") (pintype "passive"))
      (node (ref "NAND4") (pin "5") (pinfunction "I1_5") (pintype "input"))
      (node (ref "R4.1") (pin "9") (pinfunction "2_9") (pintype "passive"))
    )
    (net (code "44") (name "Net-(NAND4B-O)") (class "Default")
      (node (ref "L4.4") (pin "A") (pinfunction "A_A") (pintype "passive"))
      (node (ref "NAND4") (pin "6") (pinfunction "O_6") (pintype "output"))
      (node (ref "R4.3") (pin "4") (pinfunction "1_4") (pintype "passive"))
    )
    (net (code "45") (name "Net-(NAND4C-I0)") (class "Default")
      (node (ref "H4.2") (pin "1") (pinfunction "1_1") (pintype "passive"))
      (node (ref "H4.2") (pin "2") (pinfunction "2_2") (pintype "passive"))
      (node (ref "NAND4") (pin "9") (pinfunction "I0_9") (pintype "input"))
      (node (ref "R4.1") (pin "16") (pinfunction "2_16") (pintype "passive"))
    )
    (net (code "46") (name "Net-(NAND4C-I1)") (class "Default")
      (node (ref "H4.2") (pin "3") (pinfunction "3_3") (pintype "passive"))
      (node (ref "H4.2") (pin "4") (pinfunction "4_4") (pintype "passive"))
      (node (ref "NAND4") (pin "10") (pinfunction "I1_10") (pintype "input"))
      (node (ref "R4.1") (pin "15") (pinfunction "2_15") (pintype "passive"))
    )
    (net (code "47") (name "Net-(NAND4C-O)") (class "Default")
      (node (ref "L4.1") (pin "A") (pinfunction "A_A") (pintype "passive"))
      (node (ref "NAND4") (pin "8") (pinfunction "O_8") (pintype "output"))
      (node (ref "R4.3") (pin "1") (pinfunction "1_1") (pintype "passive"))
    )
    (net (code "48") (name "Net-(NAND4D-I0)") (class "Default")
      (node (ref "H4.2") (pin "7") (pinfunction "7_7") (pintype "passive"))
      (node (ref "H4.2") (pin "8") (pinfunction "8_8") (pintype "passive"))
      (node (ref "NAND4") (pin "12") (pinfunction "I0_12") (pintype "input"))
      (node (ref "R4.1") (pin "13") (pinfunction "2_13") (pintype "passive"))
    )
    (net (code "49") (name "Net-(NAND4D-I1)") (class "Default")
      (node (ref "H4.2") (pin "5") (pinfunction "5_5") (pintype "passive"))
      (node (ref "H4.2") (pin "6") (pinfunction "6_6") (pintype "passive"))
      (node (ref "NAND4") (pin "13") (pinfunction "I1_13") (pintype "input"))
      (node (ref "R4.1") (pin "14") (pinfunction "2_14") (pintype "passive"))
    )
    (net (code "50") (name "Net-(NAND4D-O)") (class "Default")
      (node (ref "L4.2") (pin "A") (pinfunction "A_A") (pintype "passive"))
      (node (ref "NAND4") (pin "11") (pinfunction "O_11") (pintype "output"))
      (node (ref "R4.3") (pin "2") (pinfunction "1_2") (pintype "passive"))
    )
    (net (code "51") (name "Net-(R1.2A-2)") (class "Default")
      (node (ref "L1.1") (pin "C") (pinfunction "C_C") (pintype "passive"))
      (node (ref "R1.2") (pin "8") (pinfunction "2_8") (pintype "passive"))
    )
    (net (code "52") (name "Net-(R1.2B-2)") (class "Default")
      (node (ref "L1.2") (pin "C") (pinfunction "C_C") (pintype "passive"))
      (node (ref "R1.2") (pin "7") (pinfunction "2_7") (pintype "passive"))
    )
    (net (code "53") (name "Net-(R1.2C-2)") (class "Default")
      (node (ref "L1.3") (pin "C") (pinfunction "C_C") (pintype "passive"))
      (node (ref "R1.2") (pin "6") (pinfunction "2_6") (pintype "passive"))
    )
    (net (code "54") (name "Net-(R1.2D-2)") (class "Default")
      (node (ref "L1.4") (pin "C") (pinfunction "C_C") (pintype "passive"))
      (node (ref "R1.2") (pin "5") (pinfunction "2_5") (pintype "passive"))
    )
    (net (code "55") (name "Net-(R1.3A-2)") (class "Default")
      (node (ref "H1.3") (pin "1") (pinfunction "1_1") (pintype "passive"))
      (node (ref "H1.3") (pin "2") (pinfunction "2_2") (pintype "passive"))
      (node (ref "H1.3") (pin "3") (pinfunction "3_3") (pintype "passive"))
      (node (ref "H1.3") (pin "4") (pinfunction "4_4") (pintype "passive"))
      (node (ref "R1.3") (pin "8") (pinfunction "2_8") (pintype "passive"))
    )
    (net (code "56") (name "Net-(R1.3B-2)") (class "Default")
      (node (ref "H1.3") (pin "5") (pinfunction "5_5") (pintype "passive"))
      (node (ref "H1.3") (pin "6") (pinfunction "6_6") (pintype "passive"))
      (node (ref "H1.3") (pin "7") (pinfunction "7_7") (pintype "passive"))
      (node (ref "H1.3") (pin "8") (pinfunction "8_8") (pintype "passive"))
      (node (ref "R1.3") (pin "7") (pinfunction "2_7") (pintype "passive"))
    )
    (net (code "57") (name "Net-(R1.3C-2)") (class "Default")
      (node (ref "H1.3") (pin "10") (pinfunction "10_10") (pintype "passive"))
      (node (ref "H1.3") (pin "11") (pinfunction "11_11") (pintype "passive"))
      (node (ref "H1.3") (pin "12") (pinfunction "12_12") (pintype "passive"))
      (node (ref "H1.3") (pin "9") (pinfunction "9_9") (pintype "passive"))
      (node (ref "R1.3") (pin "6") (pinfunction "2_6") (pintype "passive"))
    )
    (net (code "58") (name "Net-(R1.3D-2)") (class "Default")
      (node (ref "H1.3") (pin "13") (pinfunction "13_13") (pintype "passive"))
      (node (ref "H1.3") (pin "14") (pinfunction "14_14") (pintype "passive"))
      (node (ref "H1.3") (pin "15") (pinfunction "15_15") (pintype "passive"))
      (node (ref "H1.3") (pin "16") (pinfunction "16_16") (pintype "passive"))
      (node (ref "R1.3") (pin "5") (pinfunction "2_5") (pintype "passive"))
    )
    (net (code "59") (name "Net-(R2.2A-2)") (class "Default")
      (node (ref "L2.1") (pin "C") (pinfunction "C_C") (pintype "passive"))
      (node (ref "R2.2") (pin "8") (pinfunction "2_8") (pintype "passive"))
    )
    (net (code "60") (name "Net-(R2.2B-2)") (class "Default")
      (node (ref "L2.2") (pin "C") (pinfunction "C_C") (pintype "passive"))
      (node (ref "R2.2") (pin "7") (pinfunction "2_7") (pintype "passive"))
    )
    (net (code "61") (name "Net-(R2.2C-2)") (class "Default")
      (node (ref "L2.3") (pin "C") (pinfunction "C_C") (pintype "passive"))
      (node (ref "R2.2") (pin "6") (pinfunction "2_6") (pintype "passive"))
    )
    (net (code "62") (name "Net-(R2.2D-2)") (class "Default")
      (node (ref "L2.4") (pin "C") (pinfunction "C_C") (pintype "passive"))
      (node (ref "R2.2") (pin "5") (pinfunction "2_5") (pintype "passive"))
    )
    (net (code "63") (name "Net-(R2.3A-2)") (class "Default")
      (node (ref "H2.3") (pin "1") (pinfunction "1_1") (pintype "passive"))
      (node (ref "H2.3") (pin "2") (pinfunction "2_2") (pintype "passive"))
      (node (ref "H2.3") (pin "3") (pinfunction "3_3") (pintype "passive"))
      (node (ref "H2.3") (pin "4") (pinfunction "4_4") (pintype "passive"))
      (node (ref "R2.3") (pin "8") (pinfunction "2_8") (pintype "passive"))
    )
    (net (code "64") (name "Net-(R2.3B-2)") (class "Default")
      (node (ref "H2.3") (pin "5") (pinfunction "5_5") (pintype "passive"))
      (node (ref "H2.3") (pin "6") (pinfunction "6_6") (pintype "passive"))
      (node (ref "H2.3") (pin "7") (pinfunction "7_7") (pintype "passive"))
      (node (ref "H2.3") (pin "8") (pinfunction "8_8") (pintype "passive"))
      (node (ref "R2.3") (pin "7") (pinfunction "2_7") (pintype "passive"))
    )
    (net (code "65") (name "Net-(R2.3C-2)") (class "Default")
      (node (ref "H2.3") (pin "10") (pinfunction "10_10") (pintype "passive"))
      (node (ref "H2.3") (pin "11") (pinfunction "11_11") (pintype "passive"))
      (node (ref "H2.3") (pin "12") (pinfunction "12_12") (pintype "passive"))
      (node (ref "H2.3") (pin "9") (pinfunction "9_9") (pintype "passive"))
      (node (ref "R2.3") (pin "6") (pinfunction "2_6") (pintype "passive"))
    )
    (net (code "66") (name "Net-(R2.3D-2)") (class "Default")
      (node (ref "H2.3") (pin "13") (pinfunction "13_13") (pintype "passive"))
      (node (ref "H2.3") (pin "14") (pinfunction "14_14") (pintype "passive"))
      (node (ref "H2.3") (pin "15") (pinfunction "15_15") (pintype "passive"))
      (node (ref "H2.3") (pin "16") (pinfunction "16_16") (pintype "passive"))
      (node (ref "R2.3") (pin "5") (pinfunction "2_5") (pintype "passive"))
    )
    (net (code "67") (name "Net-(R3.2A-2)") (class "Default")
      (node (ref "L3.1") (pin "C") (pinfunction "C_C") (pintype "passive"))
      (node (ref "R3.2") (pin "8") (pinfunction "2_8") (pintype "passive"))
    )
    (net (code "68") (name "Net-(R3.2B-2)") (class "Default")
      (node (ref "L3.2") (pin "C") (pinfunction "C_C") (pintype "passive"))
      (node (ref "R3.2") (pin "7") (pinfunction "2_7") (pintype "passive"))
    )
    (net (code "69") (name "Net-(R3.2C-2)") (class "Default")
      (node (ref "L3.3") (pin "C") (pinfunction "C_C") (pintype "passive"))
      (node (ref "R3.2") (pin "6") (pinfunction "2_6") (pintype "passive"))
    )
    (net (code "70") (name "Net-(R3.2D-2)") (class "Default")
      (node (ref "L3.4") (pin "C") (pinfunction "C_C") (pintype "passive"))
      (node (ref "R3.2") (pin "5") (pinfunction "2_5") (pintype "passive"))
    )
    (net (code "71") (name "Net-(R3.3A-2)") (class "Default")
      (node (ref "H3.3") (pin "1") (pinfunction "1_1") (pintype "passive"))
      (node (ref "H3.3") (pin "2") (pinfunction "2_2") (pintype "passive"))
      (node (ref "H3.3") (pin "3") (pinfunction "3_3") (pintype "passive"))
      (node (ref "H3.3") (pin "4") (pinfunction "4_4") (pintype "passive"))
      (node (ref "R3.3") (pin "8") (pinfunction "2_8") (pintype "passive"))
    )
    (net (code "72") (name "Net-(R3.3B-2)") (class "Default")
      (node (ref "H3.3") (pin "5") (pinfunction "5_5") (pintype "passive"))
      (node (ref "H3.3") (pin "6") (pinfunction "6_6") (pintype "passive"))
      (node (ref "H3.3") (pin "7") (pinfunction "7_7") (pintype "passive"))
      (node (ref "H3.3") (pin "8") (pinfunction "8_8") (pintype "passive"))
      (node (ref "R3.3") (pin "7") (pinfunction "2_7") (pintype "passive"))
    )
    (net (code "73") (name "Net-(R3.3C-2)") (class "Default")
      (node (ref "H3.3") (pin "10") (pinfunction "10_10") (pintype "passive"))
      (node (ref "H3.3") (pin "11") (pinfunction "11_11") (pintype "passive"))
      (node (ref "H3.3") (pin "12") (pinfunction "12_12") (pintype "passive"))
      (node (ref "H3.3") (pin "9") (pinfunction "9_9") (pintype "passive"))
      (node (ref "R3.3") (pin "6") (pinfunction "2_6") (pintype "passive"))
    )
    (net (code "74") (name "Net-(R3.3D-2)") (class "Default")
      (node (ref "H3.3") (pin "13") (pinfunction "13_13") (pintype "passive"))
      (node (ref "H3.3") (pin "14") (pinfunction "14_14") (pintype "passive"))
      (node (ref "H3.3") (pin "15") (pinfunction "15_15") (pintype "passive"))
      (node (ref "H3.3") (pin "16") (pinfunction "16_16") (pintype "passive"))
      (node (ref "R3.3") (pin "5") (pinfunction "2_5") (pintype "passive"))
    )
    (net (code "75") (name "Net-(R4.2A-2)") (class "Default")
      (node (ref "L4.1") (pin "C") (pinfunction "C_C") (pintype "passive"))
      (node (ref "R4.2") (pin "8") (pinfunction "2_8") (pintype "passive"))
    )
    (net (code "76") (name "Net-(R4.2B-2)") (class "Default")
      (node (ref "L4.2") (pin "C") (pinfunction "C_C") (pintype "passive"))
      (node (ref "R4.2") (pin "7") (pinfunction "2_7") (pintype "passive"))
    )
    (net (code "77") (name "Net-(R4.2C-2)") (class "Default")
      (node (ref "L4.3") (pin "C") (pinfunction "C_C") (pintype "passive"))
      (node (ref "R4.2") (pin "6") (pinfunction "2_6") (pintype "passive"))
    )
    (net (code "78") (name "Net-(R4.2D-2)") (class "Default")
      (node (ref "L4.4") (pin "C") (pinfunction "C_C") (pintype "passive"))
      (node (ref "R4.2") (pin "5") (pinfunction "2_5") (pintype "passive"))
    )
    (net (code "79") (name "Net-(R4.3A-2)") (class "Default")
      (node (ref "H4.3") (pin "1") (pinfunction "1_1") (pintype "passive"))
      (node (ref "H4.3") (pin "2") (pinfunction "2_2") (pintype "passive"))
      (node (ref "H4.3") (pin "3") (pinfunction "3_3") (pintype "passive"))
      (node (ref "H4.3") (pin "4") (pinfunction "4_4") (pintype "passive"))
      (node (ref "R4.3") (pin "8") (pinfunction "2_8") (pintype "passive"))
    )
    (net (code "80") (name "Net-(R4.3B-2)") (class "Default")
      (node (ref "H4.3") (pin "5") (pinfunction "5_5") (pintype "passive"))
      (node (ref "H4.3") (pin "6") (pinfunction "6_6") (pintype "passive"))
      (node (ref "H4.3") (pin "7") (pinfunction "7_7") (pintype "passive"))
      (node (ref "H4.3") (pin "8") (pinfunction "8_8") (pintype "passive"))
      (node (ref "R4.3") (pin "7") (pinfunction "2_7") (pintype "passive"))
    )
    (net (code "81") (name "Net-(R4.3C-2)") (class "Default")
      (node (ref "H4.3") (pin "10") (pinfunction "10_10") (pintype "passive"))
      (node (ref "H4.3") (pin "11") (pinfunction "11_11") (pintype "passive"))
      (node (ref "H4.3") (pin "12") (pinfunction "12_12") (pintype "passive"))
      (node (ref "H4.3") (pin "9") (pinfunction "9_9") (pintype "passive"))
      (node (ref "R4.3") (pin "6") (pinfunction "2_6") (pintype "passive"))
    )
    (net (code "82") (name "Net-(R4.3D-2)") (class "Default")
      (node (ref "H4.3") (pin "13") (pinfunction "13_13") (pintype "passive"))
      (node (ref "H4.3") (pin "14") (pinfunction "14_14") (pintype "passive"))
      (node (ref "H4.3") (pin "15") (pinfunction "15_15") (pintype "passive"))
      (node (ref "H4.3") (pin "16") (pinfunction "16_16") (pintype "passive"))
      (node (ref "R4.3") (pin "5") (pinfunction "2_5") (pintype "passive"))
    )
    (net (code "83") (name "Net-(R5B-1)") (class "Default")
      (node (ref "H5") (pin "5") (pinfunction "5_5") (pintype "passive"))
      (node (ref "H5") (pin "6") (pinfunction "6_6") (pintype "passive"))
      (node (ref "H5") (pin "7") (pinfunction "7_7") (pintype "passive"))
      (node (ref "H5") (pin "8") (pinfunction "8_8") (pintype "passive"))
      (node (ref "R5") (pin "2") (pinfunction "1_2") (pintype "passive"))
      (node (ref "S2") (pin "3") (pinfunction "B_3") (pintype "bidirectional"))
      (node (ref "S2") (pin "4") (pinfunction "B_4") (pintype "bidirectional"))
    )
    (net (code "84") (name "Net-(R5C-1)") (class "Default")
      (node (ref "H5") (pin "10") (pinfunction "10_10") (pintype "passive"))
      (node (ref "H5") (pin "11") (pinfunction "11_11") (pintype "passive"))
      (node (ref "H5") (pin "12") (pinfunction "12_12") (pintype "passive"))
      (node (ref "H5") (pin "9") (pinfunction "9_9") (pintype "passive"))
      (node (ref "R5") (pin "3") (pinfunction "1_3") (pintype "passive"))
      (node (ref "S3") (pin "3") (pinfunction "B_3") (pintype "bidirectional"))
      (node (ref "S3") (pin "4") (pinfunction "B_4") (pintype "bidirectional"))
    )
    (net (code "85") (name "Net-(R5D-1)") (class "Default")
      (node (ref "H5") (pin "13") (pinfunction "13_13") (pintype "passive"))
      (node (ref "H5") (pin "14") (pinfunction "14_14") (pintype "passive"))
      (node (ref "H5") (pin "15") (pinfunction "15_15") (pintype "passive"))
      (node (ref "H5") (pin "16") (pinfunction "16_16") (pintype "passive"))
      (node (ref "R5") (pin "4") (pinfunction "1_4") (pintype "passive"))
      (node (ref "S4") (pin "3") (pinfunction "B_3") (pintype "bidirectional"))
      (node (ref "S4") (pin "4") (pinfunction "B_4") (pintype "bidirectional"))
    )
    (net (code "86") (name "VCC") (class "Default")
      (node (ref "C1") (pin "1") (pinfunction "1_1") (pintype "passive"))
      (node (ref "C2") (pin "1") (pinfunction "1_1") (pintype "passive"))
      (node (ref "H1.1") (pin "1") (pinfunction "1_1") (pintype "passive"))
      (node (ref "H1.1") (pin "2") (pinfunction "2_2") (pintype "passive"))
      (node (ref "H1.1") (pin "3") (pinfunction "3_3") (pintype "passive"))
      (node (ref "H1.1") (pin "4") (pinfunction "4_4") (pintype "passive"))
      (node (ref "H1.1") (pin "5") (pinfunction "5_5") (pintype "passive"))
      (node (ref "H1.1") (pin "6") (pinfunction "6_6") (pintype "passive"))
      (node (ref "H1.1") (pin "7") (pinfunction "7_7") (pintype "passive"))
      (node (ref "H1.1") (pin "8") (pinfunction "8_8") (pintype "passive"))
      (node (ref "H2.1") (pin "1") (pinfunction "1_1") (pintype "passive"))
      (node (ref "H2.1") (pin "2") (pinfunction "2_2") (pintype "passive"))
      (node (ref "H2.1") (pin "3") (pinfunction "3_3") (pintype "passive"))
      (node (ref "H2.1") (pin "4") (pinfunction "4_4") (pintype "passive"))
      (node (ref "H2.1") (pin "5") (pinfunction "5_5") (pintype "passive"))
      (node (ref "H2.1") (pin "6") (pinfunction "6_6") (pintype "passive"))
      (node (ref "H2.1") (pin "7") (pinfunction "7_7") (pintype "passive"))
      (node (ref "H2.1") (pin "8") (pinfunction "8_8") (pintype "passive"))
      (node (ref "H3.1") (pin "1") (pinfunction "1_1") (pintype "passive"))
      (node (ref "H3.1") (pin "2") (pinfunction "2_2") (pintype "passive"))
      (node (ref "H3.1") (pin "3") (pinfunction "3_3") (pintype "passive"))
      (node (ref "H3.1") (pin "4") (pinfunction "4_4") (pintype "passive"))
      (node (ref "H3.1") (pin "5") (pinfunction "5_5") (pintype "passive"))
      (node (ref "H3.1") (pin "6") (pinfunction "6_6") (pintype "passive"))
      (node (ref "H3.1") (pin "7") (pinfunction "7_7") (pintype "passive"))
      (node (ref "H3.1") (pin "8") (pinfunction "8_8") (pintype "passive"))
      (node (ref "H4.1") (pin "1") (pinfunction "1_1") (pintype "passive"))
      (node (ref "H4.1") (pin "2") (pinfunction "2_2") (pintype "passive"))
      (node (ref "H4.1") (pin "3") (pinfunction "3_3") (pintype "passive"))
      (node (ref "H4.1") (pin "4") (pinfunction "4_4") (pintype "passive"))
      (node (ref "H4.1") (pin "5") (pinfunction "5_5") (pintype "passive"))
      (node (ref "H4.1") (pin "6") (pinfunction "6_6") (pintype "passive"))
      (node (ref "H4.1") (pin "7") (pinfunction "7_7") (pintype "passive"))
      (node (ref "H4.1") (pin "8") (pinfunction "8_8") (pintype "passive"))
      (node (ref "NAND1") (pin "14") (pinfunction "VCC_14") (pintype "power_in"))
      (node (ref "NAND2") (pin "14") (pinfunction "VCC_14") (pintype "power_in"))
      (node (ref "NAND3") (pin "14") (pinfunction "VCC_14") (pintype "power_in"))
      (node (ref "NAND4") (pin "14") (pinfunction "VCC_14") (pintype "power_in"))
      (node (ref "PWR") (pin "1") (pinfunction "1_1") (pintype "passive"))
      (node (ref "S1") (pin "1") (pinfunction "A_1") (pintype "bidirectional"))
      (node (ref "S1") (pin "2") (pinfunction "A_2") (pintype "bidirectional"))
      (node (ref "S2") (pin "1") (pinfunction "A_1") (pintype "bidirectional"))
      (node (ref "S2") (pin "2") (pinfunction "A_2") (pintype "bidirectional"))
      (node (ref "S3") (pin "1") (pinfunction "A_1") (pintype "bidirectional"))
      (node (ref "S3") (pin "2") (pinfunction "A_2") (pintype "bidirectional"))
      (node (ref "S4") (pin "1") (pinfunction "A_1") (pintype "bidirectional"))
      (node (ref "S4") (pin "2") (pinfunction "A_2") (pintype "bidirectional"))
      (node (ref "USB") (pin "1") (pinfunction "VCC_1") (pintype "bidirectional"))
    )
    (net (code "87") (name "unconnected-(USB-D+-Pad3)") (class "Default")
      (node (ref "USB") (pin "3") (pinfunction "D+_3") (pintype "bidirectional"))
    )
    (net (code "88") (name "unconnected-(USB-D--Pad2)") (class "Default")
      (node (ref "USB") (pin "2") (pinfunction "D-_2") (pintype "bidirectional"))
    )
    (net (code "89") (name "unconnected-(USB-ID-Pad4)") (class "Default")
      (node (ref "USB") (pin "4") (pinfunction "ID_4") (pintype "bidirectional"))
    )
  )
)
